# FPGA_0.net
KiCad netlist of a schematic drawn in Altium Designer
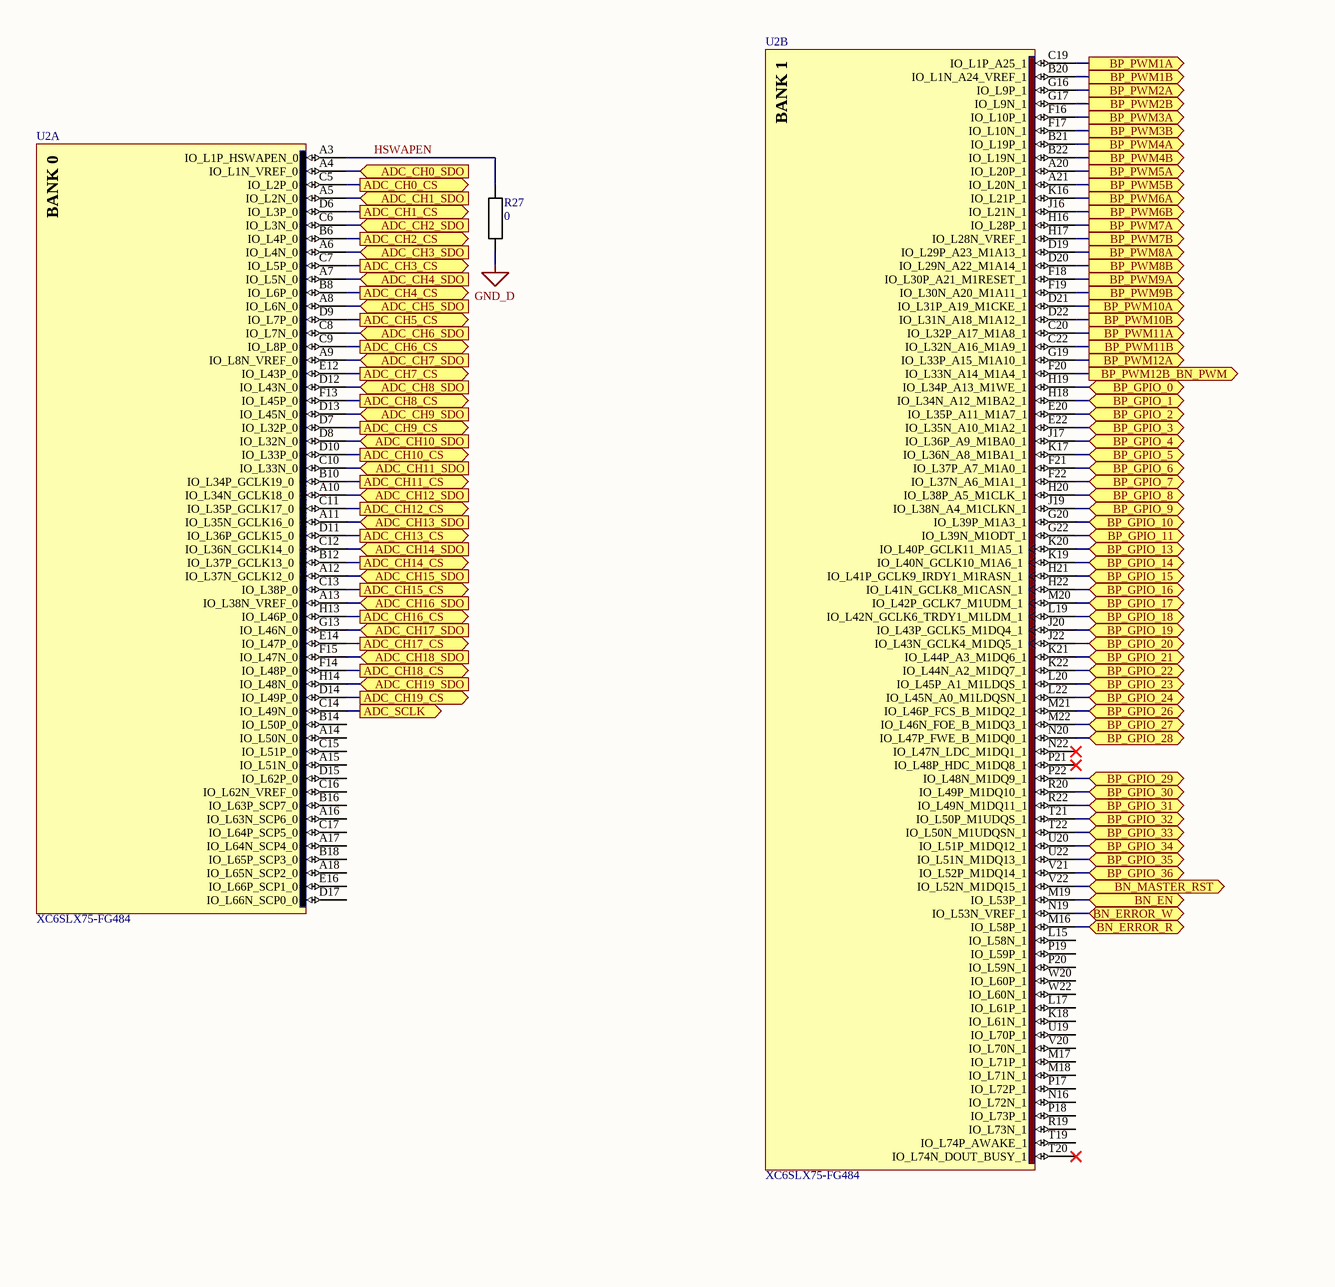
[diagram p0: FPGA_0.SchDoc, left]
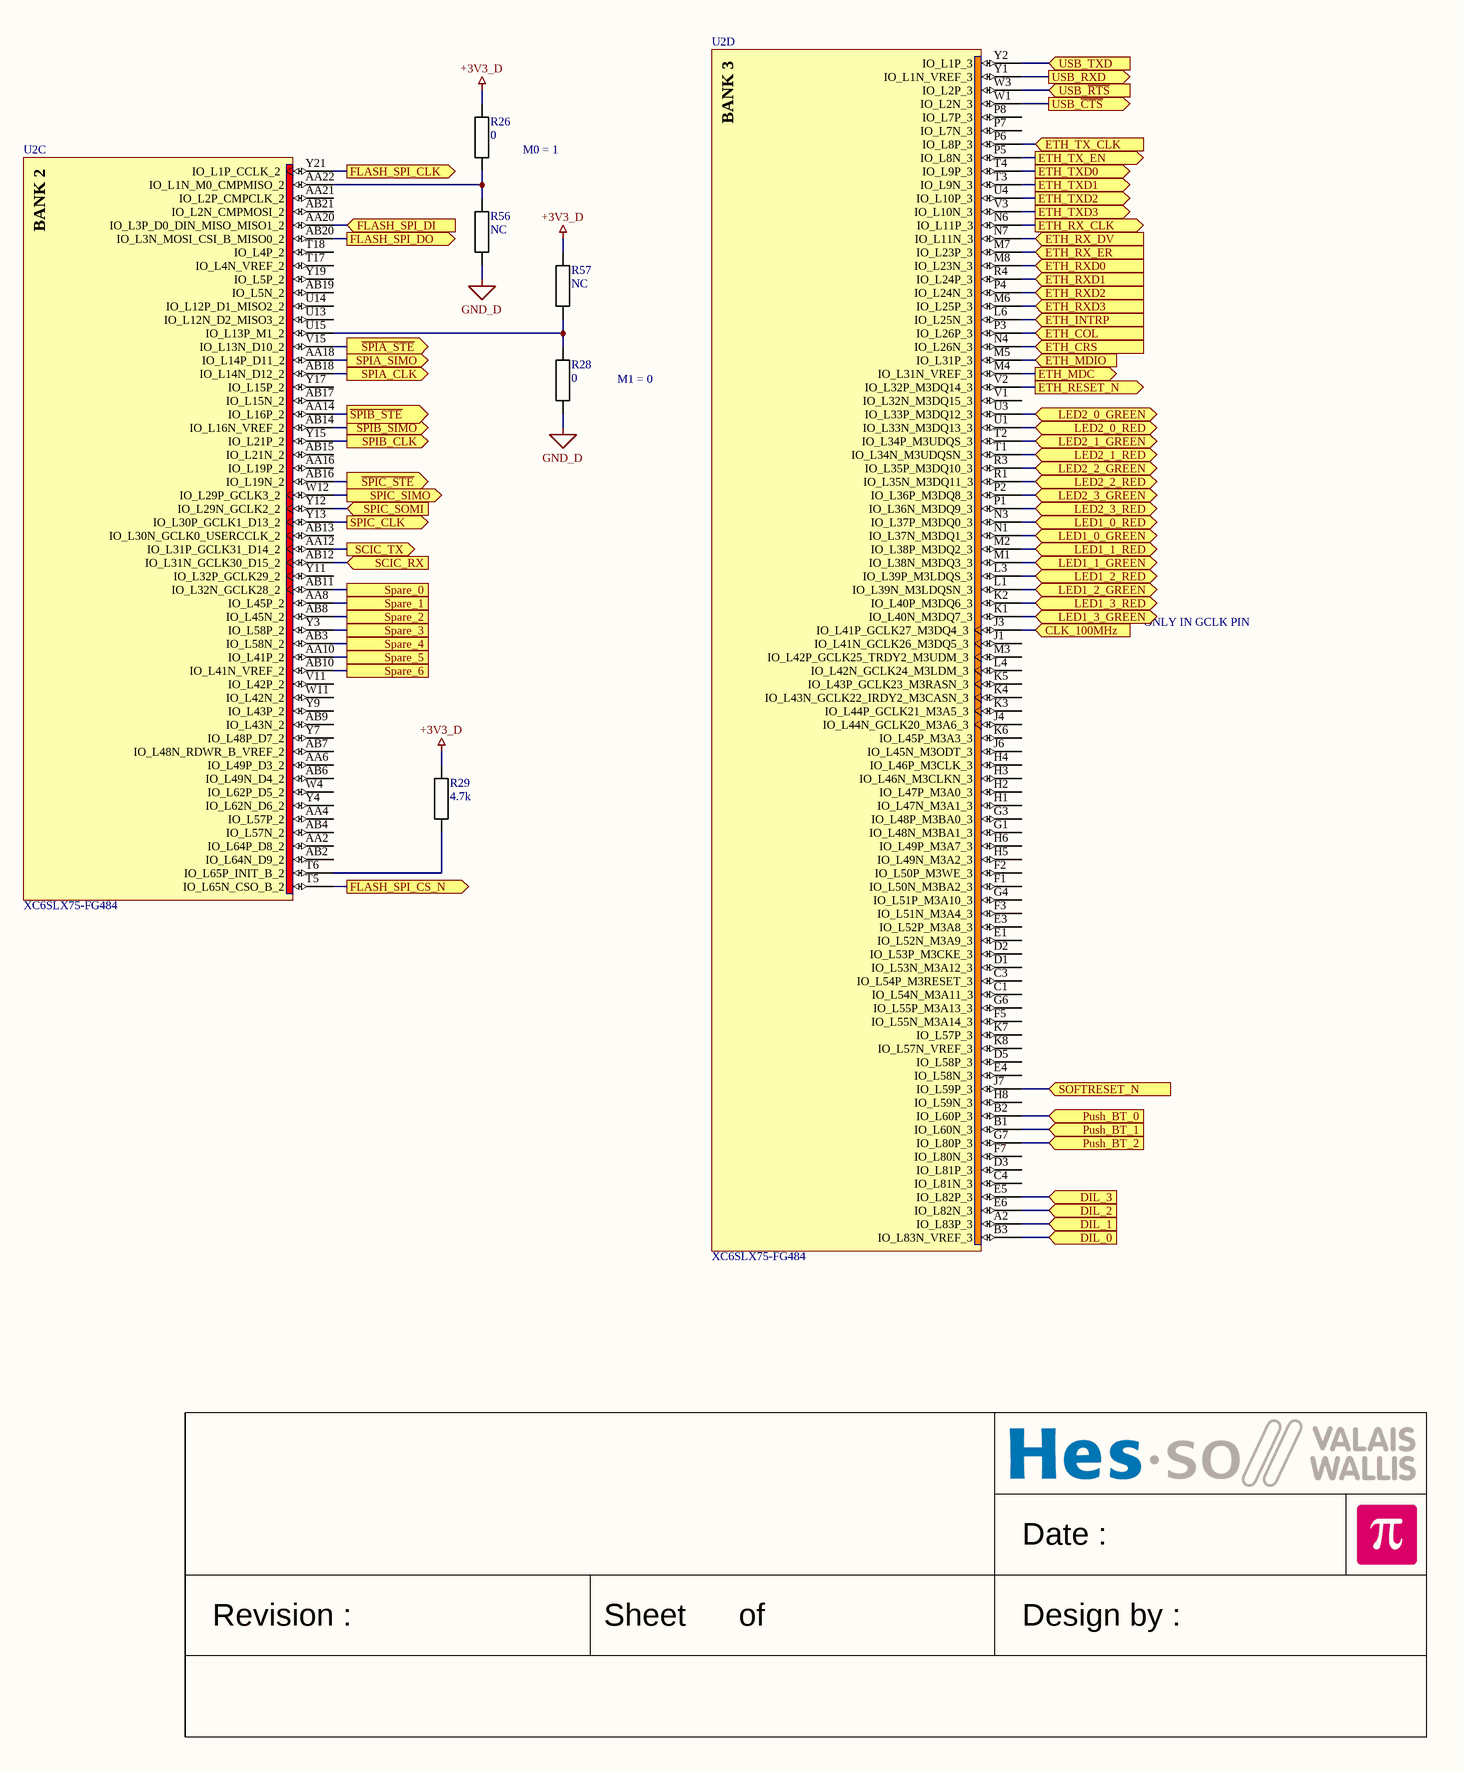
[diagram p1: FPGA_0.SchDoc, right]

(export (version "E")
  (design (tool "Eeschema 10.0.6"))
  (components
    (comp (ref "R26")
      (value "0")
      (footprint "RESISTOR 2012 REFLOW")
      (description "Resistor 1% 50V 125mW 2012(0805)")
      (libsource (lib "Resistor") (part "Resistor"))
    )
    (comp (ref "R27")
      (value "0")
      (footprint "RESISTOR 2012 REFLOW")
      (description "Resistor 1% 50V 125mW 2012(0805)")
      (libsource (lib "Resistor") (part "Resistor"))
    )
    (comp (ref "R28")
      (value "0")
      (footprint "RESISTOR 2012 REFLOW")
      (description "Resistor 1% 50V 125mW 2012(0805)")
      (libsource (lib "Resistor") (part "Resistor"))
    )
    (comp (ref "R29")
      (value "4.7k")
      (footprint "RESISTOR 2012 REFLOW")
      (description "Resistor 1% 50V 125mW 2012(0805)")
      (libsource (lib "Resistor") (part "Resistor"))
    )
    (comp (ref "R56")
      (value "NC")
      (footprint "RESISTOR 2012 REFLOW")
      (description "Resistor 1% 50V 125mW 2012(0805)")
      (libsource (lib "Resistor") (part "Resistor"))
    )
    (comp (ref "R57")
      (value "NC")
      (footprint "RESISTOR 2012 REFLOW")
      (description "Resistor 1% 50V 125mW 2012(0805)")
      (libsource (lib "Resistor") (part "Resistor"))
    )
    (comp (ref "U2")
      (value "XC6SLX75-FG484")
      (footprint "BGA484 P1.0 C23X23 H2.2")
      (description "Spartan-6 LXT 1.2V FPGA, 268 User I/Os, 484-Ball Fine-Pitch BGA (1.0mm Pitch)")
      (libsource (lib "Processor") (part "XC6SLX75-FG484"))
    )
  )
  (nets
    (net (code "1") (name "+3V3_D") (class "Default")
      (node (ref "R26") (pin "2") (pinfunction "2_2") (pintype "passive"))
      (node (ref "R29") (pin "2") (pinfunction "2_2") (pintype "passive"))
      (node (ref "R57") (pin "2") (pinfunction "2_2") (pintype "passive"))
    )
    (net (code "2") (name "/ADC_CH0_CS") (class "Default")
      (node (ref "U2") (pin "C5") (pinfunction "IO_L2P_0_C5") (pintype "bidirectional"))
    )
    (net (code "3") (name "/ADC_CH0_SDO") (class "Default")
      (node (ref "U2") (pin "A4") (pinfunction "IO_L1N_VREF_0_A4") (pintype "bidirectional"))
    )
    (net (code "4") (name "/ADC_CH1_CS") (class "Default")
      (node (ref "U2") (pin "D6") (pinfunction "IO_L3P_0_D6") (pintype "bidirectional"))
    )
    (net (code "5") (name "/ADC_CH1_SDO") (class "Default")
      (node (ref "U2") (pin "A5") (pinfunction "IO_L2N_0_A5") (pintype "bidirectional"))
    )
    (net (code "6") (name "/ADC_CH2_CS") (class "Default")
      (node (ref "U2") (pin "B6") (pinfunction "IO_L4P_0_B6") (pintype "bidirectional"))
    )
    (net (code "7") (name "/ADC_CH2_SDO") (class "Default")
      (node (ref "U2") (pin "C6") (pinfunction "IO_L3N_0_C6") (pintype "bidirectional"))
    )
    (net (code "8") (name "/ADC_CH3_CS") (class "Default")
      (node (ref "U2") (pin "C7") (pinfunction "IO_L5P_0_C7") (pintype "bidirectional"))
    )
    (net (code "9") (name "/ADC_CH3_SDO") (class "Default")
      (node (ref "U2") (pin "A6") (pinfunction "IO_L4N_0_A6") (pintype "bidirectional"))
    )
    (net (code "10") (name "/ADC_CH4_CS") (class "Default")
      (node (ref "U2") (pin "B8") (pinfunction "IO_L6P_0_B8") (pintype "bidirectional"))
    )
    (net (code "11") (name "/ADC_CH4_SDO") (class "Default")
      (node (ref "U2") (pin "A7") (pinfunction "IO_L5N_0_A7") (pintype "bidirectional"))
    )
    (net (code "12") (name "/ADC_CH5_CS") (class "Default")
      (node (ref "U2") (pin "D9") (pinfunction "IO_L7P_0_D9") (pintype "bidirectional"))
    )
    (net (code "13") (name "/ADC_CH5_SDO") (class "Default")
      (node (ref "U2") (pin "A8") (pinfunction "IO_L6N_0_A8") (pintype "bidirectional"))
    )
    (net (code "14") (name "/ADC_CH6_CS") (class "Default")
      (node (ref "U2") (pin "C9") (pinfunction "IO_L8P_0_C9") (pintype "bidirectional"))
    )
    (net (code "15") (name "/ADC_CH6_SDO") (class "Default")
      (node (ref "U2") (pin "C8") (pinfunction "IO_L7N_0_C8") (pintype "bidirectional"))
    )
    (net (code "16") (name "/ADC_CH7_CS") (class "Default")
      (node (ref "U2") (pin "E12") (pinfunction "IO_L43P_0_E12") (pintype "bidirectional"))
    )
    (net (code "17") (name "/ADC_CH7_SDO") (class "Default")
      (node (ref "U2") (pin "A9") (pinfunction "IO_L8N_VREF_0_A9") (pintype "bidirectional"))
    )
    (net (code "18") (name "/ADC_CH8_CS") (class "Default")
      (node (ref "U2") (pin "F13") (pinfunction "IO_L45P_0_F13") (pintype "bidirectional"))
    )
    (net (code "19") (name "/ADC_CH8_SDO") (class "Default")
      (node (ref "U2") (pin "D12") (pinfunction "IO_L43N_0_D12") (pintype "bidirectional"))
    )
    (net (code "20") (name "/ADC_CH9_CS") (class "Default")
      (node (ref "U2") (pin "D7") (pinfunction "IO_L32P_0_D7") (pintype "bidirectional"))
    )
    (net (code "21") (name "/ADC_CH9_SDO") (class "Default")
      (node (ref "U2") (pin "D13") (pinfunction "IO_L45N_0_D13") (pintype "bidirectional"))
    )
    (net (code "22") (name "/ADC_CH10_CS") (class "Default")
      (node (ref "U2") (pin "D10") (pinfunction "IO_L33P_0_D10") (pintype "bidirectional"))
    )
    (net (code "23") (name "/ADC_CH10_SDO") (class "Default")
      (node (ref "U2") (pin "D8") (pinfunction "IO_L32N_0_D8") (pintype "bidirectional"))
    )
    (net (code "24") (name "/ADC_CH11_CS") (class "Default")
      (node (ref "U2") (pin "B10") (pinfunction "IO_L34P_GCLK19_0_B10") (pintype "bidirectional"))
    )
    (net (code "25") (name "/ADC_CH11_SDO") (class "Default")
      (node (ref "U2") (pin "C10") (pinfunction "IO_L33N_0_C10") (pintype "bidirectional"))
    )
    (net (code "26") (name "/ADC_CH12_CS") (class "Default")
      (node (ref "U2") (pin "C11") (pinfunction "IO_L35P_GCLK17_0_C11") (pintype "bidirectional"))
    )
    (net (code "27") (name "/ADC_CH12_SDO") (class "Default")
      (node (ref "U2") (pin "A10") (pinfunction "IO_L34N_GCLK18_0_A10") (pintype "bidirectional"))
    )
    (net (code "28") (name "/ADC_CH13_CS") (class "Default")
      (node (ref "U2") (pin "D11") (pinfunction "IO_L36P_GCLK15_0_D11") (pintype "bidirectional"))
    )
    (net (code "29") (name "/ADC_CH13_SDO") (class "Default")
      (node (ref "U2") (pin "A11") (pinfunction "IO_L35N_GCLK16_0_A11") (pintype "bidirectional"))
    )
    (net (code "30") (name "/ADC_CH14_CS") (class "Default")
      (node (ref "U2") (pin "B12") (pinfunction "IO_L37P_GCLK13_0_B12") (pintype "bidirectional"))
    )
    (net (code "31") (name "/ADC_CH14_SDO") (class "Default")
      (node (ref "U2") (pin "C12") (pinfunction "IO_L36N_GCLK14_0_C12") (pintype "bidirectional"))
    )
    (net (code "32") (name "/ADC_CH15_CS") (class "Default")
      (node (ref "U2") (pin "C13") (pinfunction "IO_L38P_0_C13") (pintype "bidirectional"))
    )
    (net (code "33") (name "/ADC_CH15_SDO") (class "Default")
      (node (ref "U2") (pin "A12") (pinfunction "IO_L37N_GCLK12_0_A12") (pintype "bidirectional"))
    )
    (net (code "34") (name "/ADC_CH16_CS") (class "Default")
      (node (ref "U2") (pin "H13") (pinfunction "IO_L46P_0_H13") (pintype "bidirectional"))
    )
    (net (code "35") (name "/ADC_CH16_SDO") (class "Default")
      (node (ref "U2") (pin "A13") (pinfunction "IO_L38N_VREF_0_A13") (pintype "bidirectional"))
    )
    (net (code "36") (name "/ADC_CH17_CS") (class "Default")
      (node (ref "U2") (pin "E14") (pinfunction "IO_L47P_0_E14") (pintype "bidirectional"))
    )
    (net (code "37") (name "/ADC_CH17_SDO") (class "Default")
      (node (ref "U2") (pin "G13") (pinfunction "IO_L46N_0_G13") (pintype "bidirectional"))
    )
    (net (code "38") (name "/ADC_CH18_CS") (class "Default")
      (node (ref "U2") (pin "F14") (pinfunction "IO_L48P_0_F14") (pintype "bidirectional"))
    )
    (net (code "39") (name "/ADC_CH18_SDO") (class "Default")
      (node (ref "U2") (pin "F15") (pinfunction "IO_L47N_0_F15") (pintype "bidirectional"))
    )
    (net (code "40") (name "/ADC_CH19_CS") (class "Default")
      (node (ref "U2") (pin "D14") (pinfunction "IO_L49P_0_D14") (pintype "bidirectional"))
    )
    (net (code "41") (name "/ADC_CH19_SDO") (class "Default")
      (node (ref "U2") (pin "H14") (pinfunction "IO_L48N_0_H14") (pintype "bidirectional"))
    )
    (net (code "42") (name "/ADC_SCLK") (class "Default")
      (node (ref "U2") (pin "C14") (pinfunction "IO_L49N_0_C14") (pintype "bidirectional"))
    )
    (net (code "43") (name "/BN_EN") (class "Default")
      (node (ref "U2") (pin "M19") (pinfunction "IO_L53P_1_M19") (pintype "bidirectional"))
    )
    (net (code "44") (name "/BN_ERROR_R") (class "Default")
      (node (ref "U2") (pin "M16") (pinfunction "IO_L58P_1_M16") (pintype "bidirectional"))
    )
    (net (code "45") (name "/BN_ERROR_W") (class "Default")
      (node (ref "U2") (pin "N19") (pinfunction "IO_L53N_VREF_1_N19") (pintype "bidirectional"))
    )
    (net (code "46") (name "/BN_MASTER_RST") (class "Default")
      (node (ref "U2") (pin "V22") (pinfunction "IO_L52N_M1DQ15_1_V22") (pintype "bidirectional"))
    )
    (net (code "47") (name "/BP_GPIO_0") (class "Default")
      (node (ref "U2") (pin "H19") (pinfunction "IO_L34P_A13_M1WE_1_H19") (pintype "bidirectional"))
    )
    (net (code "48") (name "/BP_GPIO_1") (class "Default")
      (node (ref "U2") (pin "H18") (pinfunction "IO_L34N_A12_M1BA2_1_H18") (pintype "bidirectional"))
    )
    (net (code "49") (name "/BP_GPIO_2") (class "Default")
      (node (ref "U2") (pin "E20") (pinfunction "IO_L35P_A11_M1A7_1_E20") (pintype "bidirectional"))
    )
    (net (code "50") (name "/BP_GPIO_3") (class "Default")
      (node (ref "U2") (pin "E22") (pinfunction "IO_L35N_A10_M1A2_1_E22") (pintype "bidirectional"))
    )
    (net (code "51") (name "/BP_GPIO_4") (class "Default")
      (node (ref "U2") (pin "J17") (pinfunction "IO_L36P_A9_M1BA0_1_J17") (pintype "bidirectional"))
    )
    (net (code "52") (name "/BP_GPIO_5") (class "Default")
      (node (ref "U2") (pin "K17") (pinfunction "IO_L36N_A8_M1BA1_1_K17") (pintype "bidirectional"))
    )
    (net (code "53") (name "/BP_GPIO_6") (class "Default")
      (node (ref "U2") (pin "F21") (pinfunction "IO_L37P_A7_M1A0_1_F21") (pintype "bidirectional"))
    )
    (net (code "54") (name "/BP_GPIO_7") (class "Default")
      (node (ref "U2") (pin "F22") (pinfunction "IO_L37N_A6_M1A1_1_F22") (pintype "bidirectional"))
    )
    (net (code "55") (name "/BP_GPIO_8") (class "Default")
      (node (ref "U2") (pin "H20") (pinfunction "IO_L38P_A5_M1CLK_1_H20") (pintype "bidirectional"))
    )
    (net (code "56") (name "/BP_GPIO_9") (class "Default")
      (node (ref "U2") (pin "J19") (pinfunction "IO_L38N_A4_M1CLKN_1_J19") (pintype "bidirectional"))
    )
    (net (code "57") (name "/BP_GPIO_10") (class "Default")
      (node (ref "U2") (pin "G20") (pinfunction "IO_L39P_M1A3_1_G20") (pintype "bidirectional"))
    )
    (net (code "58") (name "/BP_GPIO_11") (class "Default")
      (node (ref "U2") (pin "G22") (pinfunction "IO_L39N_M1ODT_1_G22") (pintype "bidirectional"))
    )
    (net (code "59") (name "/BP_GPIO_13") (class "Default")
      (node (ref "U2") (pin "K20") (pinfunction "IO_L40P_GCLK11_M1A5_1_K20") (pintype "bidirectional"))
    )
    (net (code "60") (name "/BP_GPIO_14") (class "Default")
      (node (ref "U2") (pin "K19") (pinfunction "IO_L40N_GCLK10_M1A6_1_K19") (pintype "bidirectional"))
    )
    (net (code "61") (name "/BP_GPIO_15") (class "Default")
      (node (ref "U2") (pin "H21") (pinfunction "IO_L41P_GCLK9_IRDY1_M1RASN_1_H21") (pintype "bidirectional"))
    )
    (net (code "62") (name "/BP_GPIO_16") (class "Default")
      (node (ref "U2") (pin "H22") (pinfunction "IO_L41N_GCLK8_M1CASN_1_H22") (pintype "bidirectional"))
    )
    (net (code "63") (name "/BP_GPIO_17") (class "Default")
      (node (ref "U2") (pin "M20") (pinfunction "IO_L42P_GCLK7_M1UDM_1_M20") (pintype "bidirectional"))
    )
    (net (code "64") (name "/BP_GPIO_18") (class "Default")
      (node (ref "U2") (pin "L19") (pinfunction "IO_L42N_GCLK6_TRDY1_M1LDM_1_L19") (pintype "bidirectional"))
    )
    (net (code "65") (name "/BP_GPIO_19") (class "Default")
      (node (ref "U2") (pin "J20") (pinfunction "IO_L43P_GCLK5_M1DQ4_1_J20") (pintype "bidirectional"))
    )
    (net (code "66") (name "/BP_GPIO_20") (class "Default")
      (node (ref "U2") (pin "J22") (pinfunction "IO_L43N_GCLK4_M1DQ5_1_J22") (pintype "bidirectional"))
    )
    (net (code "67") (name "/BP_GPIO_21") (class "Default")
      (node (ref "U2") (pin "K21") (pinfunction "IO_L44P_A3_M1DQ6_1_K21") (pintype "bidirectional"))
    )
    (net (code "68") (name "/BP_GPIO_22") (class "Default")
      (node (ref "U2") (pin "K22") (pinfunction "IO_L44N_A2_M1DQ7_1_K22") (pintype "bidirectional"))
    )
    (net (code "69") (name "/BP_GPIO_23") (class "Default")
      (node (ref "U2") (pin "L20") (pinfunction "IO_L45P_A1_M1LDQS_1_L20") (pintype "bidirectional"))
    )
    (net (code "70") (name "/BP_GPIO_24") (class "Default")
      (node (ref "U2") (pin "L22") (pinfunction "IO_L45N_A0_M1LDQSN_1_L22") (pintype "bidirectional"))
    )
    (net (code "71") (name "/BP_GPIO_26") (class "Default")
      (node (ref "U2") (pin "M21") (pinfunction "IO_L46P_FCS_B_M1DQ2_1_M21") (pintype "bidirectional"))
    )
    (net (code "72") (name "/BP_GPIO_27") (class "Default")
      (node (ref "U2") (pin "M22") (pinfunction "IO_L46N_FOE_B_M1DQ3_1_M22") (pintype "bidirectional"))
    )
    (net (code "73") (name "/BP_GPIO_28") (class "Default")
      (node (ref "U2") (pin "N20") (pinfunction "IO_L47P_FWE_B_M1DQ0_1_N20") (pintype "bidirectional"))
    )
    (net (code "74") (name "/BP_GPIO_29") (class "Default")
      (node (ref "U2") (pin "P22") (pinfunction "IO_L48N_M1DQ9_1_P22") (pintype "bidirectional"))
    )
    (net (code "75") (name "/BP_GPIO_30") (class "Default")
      (node (ref "U2") (pin "R20") (pinfunction "IO_L49P_M1DQ10_1_R20") (pintype "bidirectional"))
    )
    (net (code "76") (name "/BP_GPIO_31") (class "Default")
      (node (ref "U2") (pin "R22") (pinfunction "IO_L49N_M1DQ11_1_R22") (pintype "bidirectional"))
    )
    (net (code "77") (name "/BP_GPIO_32") (class "Default")
      (node (ref "U2") (pin "T21") (pinfunction "IO_L50P_M1UDQS_1_T21") (pintype "bidirectional"))
    )
    (net (code "78") (name "/BP_GPIO_33") (class "Default")
      (node (ref "U2") (pin "T22") (pinfunction "IO_L50N_M1UDQSN_1_T22") (pintype "bidirectional"))
    )
    (net (code "79") (name "/BP_GPIO_34") (class "Default")
      (node (ref "U2") (pin "U20") (pinfunction "IO_L51P_M1DQ12_1_U20") (pintype "bidirectional"))
    )
    (net (code "80") (name "/BP_GPIO_35") (class "Default")
      (node (ref "U2") (pin "U22") (pinfunction "IO_L51N_M1DQ13_1_U22") (pintype "bidirectional"))
    )
    (net (code "81") (name "/BP_GPIO_36") (class "Default")
      (node (ref "U2") (pin "V21") (pinfunction "IO_L52P_M1DQ14_1_V21") (pintype "bidirectional"))
    )
    (net (code "82") (name "/BP_PWM1A") (class "Default")
      (node (ref "U2") (pin "C19") (pinfunction "IO_L1P_A25_1_C19") (pintype "bidirectional"))
    )
    (net (code "83") (name "/BP_PWM1B") (class "Default")
      (node (ref "U2") (pin "B20") (pinfunction "IO_L1N_A24_VREF_1_B20") (pintype "bidirectional"))
    )
    (net (code "84") (name "/BP_PWM2A") (class "Default")
      (node (ref "U2") (pin "G16") (pinfunction "IO_L9P_1_G16") (pintype "bidirectional"))
    )
    (net (code "85") (name "/BP_PWM2B") (class "Default")
      (node (ref "U2") (pin "G17") (pinfunction "IO_L9N_1_G17") (pintype "bidirectional"))
    )
    (net (code "86") (name "/BP_PWM3A") (class "Default")
      (node (ref "U2") (pin "F16") (pinfunction "IO_L10P_1_F16") (pintype "bidirectional"))
    )
    (net (code "87") (name "/BP_PWM3B") (class "Default")
      (node (ref "U2") (pin "F17") (pinfunction "IO_L10N_1_F17") (pintype "bidirectional"))
    )
    (net (code "88") (name "/BP_PWM4A") (class "Default")
      (node (ref "U2") (pin "B21") (pinfunction "IO_L19P_1_B21") (pintype "bidirectional"))
    )
    (net (code "89") (name "/BP_PWM4B") (class "Default")
      (node (ref "U2") (pin "B22") (pinfunction "IO_L19N_1_B22") (pintype "bidirectional"))
    )
    (net (code "90") (name "/BP_PWM5A") (class "Default")
      (node (ref "U2") (pin "A20") (pinfunction "IO_L20P_1_A20") (pintype "bidirectional"))
    )
    (net (code "91") (name "/BP_PWM5B") (class "Default")
      (node (ref "U2") (pin "A21") (pinfunction "IO_L20N_1_A21") (pintype "bidirectional"))
    )
    (net (code "92") (name "/BP_PWM6A") (class "Default")
      (node (ref "U2") (pin "K16") (pinfunction "IO_L21P_1_K16") (pintype "bidirectional"))
    )
    (net (code "93") (name "/BP_PWM6B") (class "Default")
      (node (ref "U2") (pin "J16") (pinfunction "IO_L21N_1_J16") (pintype "bidirectional"))
    )
    (net (code "94") (name "/BP_PWM7A") (class "Default")
      (node (ref "U2") (pin "H16") (pinfunction "IO_L28P_1_H16") (pintype "bidirectional"))
    )
    (net (code "95") (name "/BP_PWM7B") (class "Default")
      (node (ref "U2") (pin "H17") (pinfunction "IO_L28N_VREF_1_H17") (pintype "bidirectional"))
    )
    (net (code "96") (name "/BP_PWM8A") (class "Default")
      (node (ref "U2") (pin "D19") (pinfunction "IO_L29P_A23_M1A13_1_D19") (pintype "bidirectional"))
    )
    (net (code "97") (name "/BP_PWM8B") (class "Default")
      (node (ref "U2") (pin "D20") (pinfunction "IO_L29N_A22_M1A14_1_D20") (pintype "bidirectional"))
    )
    (net (code "98") (name "/BP_PWM9A") (class "Default")
      (node (ref "U2") (pin "F18") (pinfunction "IO_L30P_A21_M1RESET_1_F18") (pintype "bidirectional"))
    )
    (net (code "99") (name "/BP_PWM9B") (class "Default")
      (node (ref "U2") (pin "F19") (pinfunction "IO_L30N_A20_M1A11_1_F19") (pintype "bidirectional"))
    )
    (net (code "100") (name "/BP_PWM10A") (class "Default")
      (node (ref "U2") (pin "D21") (pinfunction "IO_L31P_A19_M1CKE_1_D21") (pintype "bidirectional"))
    )
    (net (code "101") (name "/BP_PWM10B") (class "Default")
      (node (ref "U2") (pin "D22") (pinfunction "IO_L31N_A18_M1A12_1_D22") (pintype "bidirectional"))
    )
    (net (code "102") (name "/BP_PWM11A") (class "Default")
      (node (ref "U2") (pin "C20") (pinfunction "IO_L32P_A17_M1A8_1_C20") (pintype "bidirectional"))
    )
    (net (code "103") (name "/BP_PWM11B") (class "Default")
      (node (ref "U2") (pin "C22") (pinfunction "IO_L32N_A16_M1A9_1_C22") (pintype "bidirectional"))
    )
    (net (code "104") (name "/BP_PWM12A") (class "Default")
      (node (ref "U2") (pin "G19") (pinfunction "IO_L33P_A15_M1A10_1_G19") (pintype "bidirectional"))
    )
    (net (code "105") (name "/BP_PWM12B_BN_PWM") (class "Default")
      (node (ref "U2") (pin "F20") (pinfunction "IO_L33N_A14_M1A4_1_F20") (pintype "bidirectional"))
    )
    (net (code "106") (name "/CLK_100MHz") (class "Default")
      (node (ref "U2") (pin "J3") (pinfunction "IO_L41P_GCLK27_M3DQ4_3_J3") (pintype "bidirectional"))
    )
    (net (code "107") (name "/DIL_0") (class "Default")
      (node (ref "U2") (pin "B3") (pinfunction "IO_L83N_VREF_3_B3") (pintype "bidirectional"))
    )
    (net (code "108") (name "/DIL_1") (class "Default")
      (node (ref "U2") (pin "A2") (pinfunction "IO_L83P_3_A2") (pintype "bidirectional"))
    )
    (net (code "109") (name "/DIL_2") (class "Default")
      (node (ref "U2") (pin "E6") (pinfunction "IO_L82N_3_E6") (pintype "bidirectional"))
    )
    (net (code "110") (name "/DIL_3") (class "Default")
      (node (ref "U2") (pin "E5") (pinfunction "IO_L82P_3_E5") (pintype "bidirectional"))
    )
    (net (code "111") (name "/ETH_COL") (class "Default")
      (node (ref "U2") (pin "P3") (pinfunction "IO_L26P_3_P3") (pintype "bidirectional"))
    )
    (net (code "112") (name "/ETH_CRS") (class "Default")
      (node (ref "U2") (pin "N4") (pinfunction "IO_L26N_3_N4") (pintype "bidirectional"))
    )
    (net (code "113") (name "/ETH_INTRP") (class "Default")
      (node (ref "U2") (pin "L6") (pinfunction "IO_L25N_3_L6") (pintype "bidirectional"))
    )
    (net (code "114") (name "/ETH_MDC") (class "Default")
      (node (ref "U2") (pin "M4") (pinfunction "IO_L31N_VREF_3_M4") (pintype "bidirectional"))
    )
    (net (code "115") (name "/ETH_MDIO") (class "Default")
      (node (ref "U2") (pin "M5") (pinfunction "IO_L31P_3_M5") (pintype "bidirectional"))
    )
    (net (code "116") (name "/ETH_RESET_N") (class "Default")
      (node (ref "U2") (pin "V2") (pinfunction "IO_L32P_M3DQ14_3_V2") (pintype "bidirectional"))
    )
    (net (code "117") (name "/ETH_RXD0") (class "Default")
      (node (ref "U2") (pin "M8") (pinfunction "IO_L23N_3_M8") (pintype "bidirectional"))
    )
    (net (code "118") (name "/ETH_RXD1") (class "Default")
      (node (ref "U2") (pin "R4") (pinfunction "IO_L24P_3_R4") (pintype "bidirectional"))
    )
    (net (code "119") (name "/ETH_RXD2") (class "Default")
      (node (ref "U2") (pin "P4") (pinfunction "IO_L24N_3_P4") (pintype "bidirectional"))
    )
    (net (code "120") (name "/ETH_RXD3") (class "Default")
      (node (ref "U2") (pin "M6") (pinfunction "IO_L25P_3_M6") (pintype "bidirectional"))
    )
    (net (code "121") (name "/ETH_RX_CLK") (class "Default")
      (node (ref "U2") (pin "N6") (pinfunction "IO_L11P_3_N6") (pintype "bidirectional"))
    )
    (net (code "122") (name "/ETH_RX_DV") (class "Default")
      (node (ref "U2") (pin "N7") (pinfunction "IO_L11N_3_N7") (pintype "bidirectional"))
    )
    (net (code "123") (name "/ETH_RX_ER") (class "Default")
      (node (ref "U2") (pin "M7") (pinfunction "IO_L23P_3_M7") (pintype "bidirectional"))
    )
    (net (code "124") (name "/ETH_TXD0") (class "Default")
      (node (ref "U2") (pin "T4") (pinfunction "IO_L9P_3_T4") (pintype "bidirectional"))
    )
    (net (code "125") (name "/ETH_TXD1") (class "Default")
      (node (ref "U2") (pin "T3") (pinfunction "IO_L9N_3_T3") (pintype "bidirectional"))
    )
    (net (code "126") (name "/ETH_TXD2") (class "Default")
      (node (ref "U2") (pin "U4") (pinfunction "IO_L10P_3_U4") (pintype "bidirectional"))
    )
    (net (code "127") (name "/ETH_TXD3") (class "Default")
      (node (ref "U2") (pin "V3") (pinfunction "IO_L10N_3_V3") (pintype "bidirectional"))
    )
    (net (code "128") (name "/ETH_TX_CLK") (class "Default")
      (node (ref "U2") (pin "P6") (pinfunction "IO_L8P_3_P6") (pintype "bidirectional"))
    )
    (net (code "129") (name "/ETH_TX_EN") (class "Default")
      (node (ref "U2") (pin "P5") (pinfunction "IO_L8N_3_P5") (pintype "bidirectional"))
    )
    (net (code "130") (name "/FLASH_SPI_CLK") (class "Default")
      (node (ref "U2") (pin "Y21") (pinfunction "IO_L1P_CCLK_2_Y21") (pintype "bidirectional"))
    )
    (net (code "131") (name "/FLASH_SPI_CS_N") (class "Default")
      (node (ref "U2") (pin "T5") (pinfunction "IO_L65N_CSO_B_2_T5") (pintype "bidirectional"))
    )
    (net (code "132") (name "/FLASH_SPI_DI") (class "Default")
      (node (ref "U2") (pin "AA20") (pinfunction "IO_L3P_D0_DIN_MISO_MISO1_2_AA20") (pintype "bidirectional"))
    )
    (net (code "133") (name "/FLASH_SPI_DO") (class "Default")
      (node (ref "U2") (pin "AB20") (pinfunction "IO_L3N_MOSI_CSI_B_MISO0_2_AB20") (pintype "bidirectional"))
    )
    (net (code "134") (name "/HSWAPEN") (class "Default")
      (node (ref "R27") (pin "2") (pinfunction "2_2") (pintype "passive"))
      (node (ref "U2") (pin "A3") (pinfunction "IO_L1P_HSWAPEN_0_A3") (pintype "bidirectional"))
    )
    (net (code "135") (name "/LED1_0_GREEN") (class "Default")
      (node (ref "U2") (pin "N1") (pinfunction "IO_L37N_M3DQ1_3_N1") (pintype "bidirectional"))
    )
    (net (code "136") (name "/LED1_0_RED") (class "Default")
      (node (ref "U2") (pin "N3") (pinfunction "IO_L37P_M3DQ0_3_N3") (pintype "bidirectional"))
    )
    (net (code "137") (name "/LED1_1_GREEN") (class "Default")
      (node (ref "U2") (pin "M1") (pinfunction "IO_L38N_M3DQ3_3_M1") (pintype "bidirectional"))
    )
    (net (code "138") (name "/LED1_1_RED") (class "Default")
      (node (ref "U2") (pin "M2") (pinfunction "IO_L38P_M3DQ2_3_M2") (pintype "bidirectional"))
    )
    (net (code "139") (name "/LED1_2_GREEN") (class "Default")
      (node (ref "U2") (pin "L1") (pinfunction "IO_L39N_M3LDQSN_3_L1") (pintype "bidirectional"))
    )
    (net (code "140") (name "/LED1_2_RED") (class "Default")
      (node (ref "U2") (pin "L3") (pinfunction "IO_L39P_M3LDQS_3_L3") (pintype "bidirectional"))
    )
    (net (code "141") (name "/LED1_3_GREEN") (class "Default")
      (node (ref "U2") (pin "K1") (pinfunction "IO_L40N_M3DQ7_3_K1") (pintype "bidirectional"))
    )
    (net (code "142") (name "/LED1_3_RED") (class "Default")
      (node (ref "U2") (pin "K2") (pinfunction "IO_L40P_M3DQ6_3_K2") (pintype "bidirectional"))
    )
    (net (code "143") (name "/LED2_0_GREEN") (class "Default")
      (node (ref "U2") (pin "U3") (pinfunction "IO_L33P_M3DQ12_3_U3") (pintype "bidirectional"))
    )
    (net (code "144") (name "/LED2_0_RED") (class "Default")
      (node (ref "U2") (pin "U1") (pinfunction "IO_L33N_M3DQ13_3_U1") (pintype "bidirectional"))
    )
    (net (code "145") (name "/LED2_1_GREEN") (class "Default")
      (node (ref "U2") (pin "T2") (pinfunction "IO_L34P_M3UDQS_3_T2") (pintype "bidirectional"))
    )
    (net (code "146") (name "/LED2_1_RED") (class "Default")
      (node (ref "U2") (pin "T1") (pinfunction "IO_L34N_M3UDQSN_3_T1") (pintype "bidirectional"))
    )
    (net (code "147") (name "/LED2_2_GREEN") (class "Default")
      (node (ref "U2") (pin "R3") (pinfunction "IO_L35P_M3DQ10_3_R3") (pintype "bidirectional"))
    )
    (net (code "148") (name "/LED2_2_RED") (class "Default")
      (node (ref "U2") (pin "R1") (pinfunction "IO_L35N_M3DQ11_3_R1") (pintype "bidirectional"))
    )
    (net (code "149") (name "/LED2_3_GREEN") (class "Default")
      (node (ref "U2") (pin "P2") (pinfunction "IO_L36P_M3DQ8_3_P2") (pintype "bidirectional"))
    )
    (net (code "150") (name "/LED2_3_RED") (class "Default")
      (node (ref "U2") (pin "P1") (pinfunction "IO_L36N_M3DQ9_3_P1") (pintype "bidirectional"))
    )
    (net (code "151") (name "/Push_BT_0") (class "Default")
      (node (ref "U2") (pin "B2") (pinfunction "IO_L60P_3_B2") (pintype "bidirectional"))
    )
    (net (code "152") (name "/Push_BT_1") (class "Default")
      (node (ref "U2") (pin "B1") (pinfunction "IO_L60N_3_B1") (pintype "bidirectional"))
    )
    (net (code "153") (name "/Push_BT_2") (class "Default")
      (node (ref "U2") (pin "G7") (pinfunction "IO_L80P_3_G7") (pintype "bidirectional"))
    )
    (net (code "154") (name "/SCIC_RX") (class "Default")
      (node (ref "U2") (pin "AB12") (pinfunction "IO_L31N_GCLK30_D15_2_AB12") (pintype "bidirectional"))
    )
    (net (code "155") (name "/SCIC_TX") (class "Default")
      (node (ref "U2") (pin "AA12") (pinfunction "IO_L31P_GCLK31_D14_2_AA12") (pintype "bidirectional"))
    )
    (net (code "156") (name "/SOFTRESET_N") (class "Default")
      (node (ref "U2") (pin "J7") (pinfunction "IO_L59P_3_J7") (pintype "bidirectional"))
    )
    (net (code "157") (name "/SPIA_CLK") (class "Default")
      (node (ref "U2") (pin "AB18") (pinfunction "IO_L14N_D12_2_AB18") (pintype "bidirectional"))
    )
    (net (code "158") (name "/SPIA_SIMO") (class "Default")
      (node (ref "U2") (pin "AA18") (pinfunction "IO_L14P_D11_2_AA18") (pintype "bidirectional"))
    )
    (net (code "159") (name "/SPIB_CLK") (class "Default")
      (node (ref "U2") (pin "Y15") (pinfunction "IO_L21P_2_Y15") (pintype "bidirectional"))
    )
    (net (code "160") (name "/SPIB_SIMO") (class "Default")
      (node (ref "U2") (pin "AB14") (pinfunction "IO_L16N_VREF_2_AB14") (pintype "bidirectional"))
    )
    (net (code "161") (name "/SPIC_CLK") (class "Default")
      (node (ref "U2") (pin "Y13") (pinfunction "IO_L30P_GCLK1_D13_2_Y13") (pintype "bidirectional"))
    )
    (net (code "162") (name "/SPIC_SIMO") (class "Default")
      (node (ref "U2") (pin "W12") (pinfunction "IO_L29P_GCLK3_2_W12") (pintype "bidirectional"))
    )
    (net (code "163") (name "/SPIC_SOMI") (class "Default")
      (node (ref "U2") (pin "Y12") (pinfunction "IO_L29N_GCLK2_2_Y12") (pintype "bidirectional"))
    )
    (net (code "164") (name "/Spare_0") (class "Default")
      (node (ref "U2") (pin "AB11") (pinfunction "IO_L32N_GCLK28_2_AB11") (pintype "bidirectional"))
    )
    (net (code "165") (name "/Spare_1") (class "Default")
      (node (ref "U2") (pin "AA8") (pinfunction "IO_L45P_2_AA8") (pintype "bidirectional"))
    )
    (net (code "166") (name "/Spare_2") (class "Default")
      (node (ref "U2") (pin "AB8") (pinfunction "IO_L45N_2_AB8") (pintype "bidirectional"))
    )
    (net (code "167") (name "/Spare_3") (class "Default")
      (node (ref "U2") (pin "Y3") (pinfunction "IO_L58P_2_Y3") (pintype "bidirectional"))
    )
    (net (code "168") (name "/Spare_4") (class "Default")
      (node (ref "U2") (pin "AB3") (pinfunction "IO_L58N_2_AB3") (pintype "bidirectional"))
    )
    (net (code "169") (name "/Spare_5") (class "Default")
      (node (ref "U2") (pin "AA10") (pinfunction "IO_L41P_2_AA10") (pintype "bidirectional"))
    )
    (net (code "170") (name "/Spare_6") (class "Default")
      (node (ref "U2") (pin "AB10") (pinfunction "IO_L41N_VREF_2_AB10") (pintype "bidirectional"))
    )
    (net (code "171") (name "/USB_RXD") (class "Default")
      (node (ref "U2") (pin "Y1") (pinfunction "IO_L1N_VREF_3_Y1") (pintype "bidirectional"))
    )
    (net (code "172") (name "/USB_TXD") (class "Default")
      (node (ref "U2") (pin "Y2") (pinfunction "IO_L1P_3_Y2") (pintype "bidirectional"))
    )
    (net (code "173") (name "/USB_~{CTS}") (class "Default")
      (node (ref "U2") (pin "W1") (pinfunction "IO_L2N_3_W1") (pintype "bidirectional"))
    )
    (net (code "174") (name "/USB_~{RTS}") (class "Default")
      (node (ref "U2") (pin "W3") (pinfunction "IO_L2P_3_W3") (pintype "bidirectional"))
    )
    (net (code "175") (name "/~{SPIA_STE}") (class "Default")
      (node (ref "U2") (pin "V15") (pinfunction "IO_L13N_D10_2_V15") (pintype "bidirectional"))
    )
    (net (code "176") (name "/~{SPIB_STE}") (class "Default")
      (node (ref "U2") (pin "AA14") (pinfunction "IO_L16P_2_AA14") (pintype "bidirectional"))
    )
    (net (code "177") (name "/~{SPIC_STE}") (class "Default")
      (node (ref "U2") (pin "AB16") (pinfunction "IO_L19N_2_AB16") (pintype "bidirectional"))
    )
    (net (code "178") (name "GND_D") (class "Default")
      (node (ref "R27") (pin "1") (pinfunction "1_1") (pintype "passive"))
      (node (ref "R28") (pin "1") (pinfunction "1_1") (pintype "passive"))
      (node (ref "R56") (pin "1") (pinfunction "1_1") (pintype "passive"))
    )
    (net (code "179") (name "Net-(U2C-IO_L1N_M0_CMPMISO_2)") (class "Default")
      (node (ref "R26") (pin "1") (pinfunction "1_1") (pintype "passive"))
      (node (ref "R56") (pin "2") (pinfunction "2_2") (pintype "passive"))
      (node (ref "U2") (pin "AA22") (pinfunction "IO_L1N_M0_CMPMISO_2_AA22") (pintype "bidirectional"))
    )
    (net (code "180") (name "Net-(U2C-IO_L13P_M1_2)") (class "Default")
      (node (ref "R28") (pin "2") (pinfunction "2_2") (pintype "passive"))
      (node (ref "R57") (pin "1") (pinfunction "1_1") (pintype "passive"))
      (node (ref "U2") (pin "U15") (pinfunction "IO_L13P_M1_2_U15") (pintype "bidirectional"))
    )
    (net (code "181") (name "Net-(U2C-IO_L65P_INIT_B_2)") (class "Default")
      (node (ref "R29") (pin "1") (pinfunction "1_1") (pintype "passive"))
      (node (ref "U2") (pin "T6") (pinfunction "IO_L65P_INIT_B_2_T6") (pintype "bidirectional"))
    )
    (net (code "182") (name "unconnected-(U2A-IO_L50N_0-PadA14)") (class "Default")
      (node (ref "U2") (pin "A14") (pinfunction "IO_L50N_0_A14") (pintype "bidirectional"))
    )
    (net (code "183") (name "unconnected-(U2A-IO_L50P_0-PadB14)") (class "Default")
      (node (ref "U2") (pin "B14") (pinfunction "IO_L50P_0_B14") (pintype "bidirectional"))
    )
    (net (code "184") (name "unconnected-(U2A-IO_L51N_0-PadA15)") (class "Default")
      (node (ref "U2") (pin "A15") (pinfunction "IO_L51N_0_A15") (pintype "bidirectional"))
    )
    (net (code "185") (name "unconnected-(U2A-IO_L51P_0-PadC15)") (class "Default")
      (node (ref "U2") (pin "C15") (pinfunction "IO_L51P_0_C15") (pintype "bidirectional"))
    )
    (net (code "186") (name "unconnected-(U2A-IO_L62N_VREF_0-PadC16)") (class "Default")
      (node (ref "U2") (pin "C16") (pinfunction "IO_L62N_VREF_0_C16") (pintype "bidirectional"))
    )
    (net (code "187") (name "unconnected-(U2A-IO_L62P_0-PadD15)") (class "Default")
      (node (ref "U2") (pin "D15") (pinfunction "IO_L62P_0_D15") (pintype "bidirectional"))
    )
    (net (code "188") (name "unconnected-(U2A-IO_L63N_SCP6_0-PadA16)") (class "Default")
      (node (ref "U2") (pin "A16") (pinfunction "IO_L63N_SCP6_0_A16") (pintype "bidirectional"))
    )
    (net (code "189") (name "unconnected-(U2A-IO_L63P_SCP7_0-PadB16)") (class "Default")
      (node (ref "U2") (pin "B16") (pinfunction "IO_L63P_SCP7_0_B16") (pintype "bidirectional"))
    )
    (net (code "190") (name "unconnected-(U2A-IO_L64N_SCP4_0-PadA17)") (class "Default")
      (node (ref "U2") (pin "A17") (pinfunction "IO_L64N_SCP4_0_A17") (pintype "bidirectional"))
    )
    (net (code "191") (name "unconnected-(U2A-IO_L64P_SCP5_0-PadC17)") (class "Default")
      (node (ref "U2") (pin "C17") (pinfunction "IO_L64P_SCP5_0_C17") (pintype "bidirectional"))
    )
    (net (code "192") (name "unconnected-(U2A-IO_L65N_SCP2_0-PadA18)") (class "Default")
      (node (ref "U2") (pin "A18") (pinfunction "IO_L65N_SCP2_0_A18") (pintype "bidirectional"))
    )
    (net (code "193") (name "unconnected-(U2A-IO_L65P_SCP3_0-PadB18)") (class "Default")
      (node (ref "U2") (pin "B18") (pinfunction "IO_L65P_SCP3_0_B18") (pintype "bidirectional"))
    )
    (net (code "194") (name "unconnected-(U2A-IO_L66N_SCP0_0-PadD17)") (class "Default")
      (node (ref "U2") (pin "D17") (pinfunction "IO_L66N_SCP0_0_D17") (pintype "bidirectional"))
    )
    (net (code "195") (name "unconnected-(U2A-IO_L66P_SCP1_0-PadE16)") (class "Default")
      (node (ref "U2") (pin "E16") (pinfunction "IO_L66P_SCP1_0_E16") (pintype "bidirectional"))
    )
    (net (code "196") (name "unconnected-(U2B-IO_L47N_LDC_M1DQ1_1-PadN22)") (class "Default")
      (node (ref "U2") (pin "N22") (pinfunction "IO_L47N_LDC_M1DQ1_1_N22") (pintype "bidirectional+no_connect"))
    )
    (net (code "197") (name "unconnected-(U2B-IO_L48P_HDC_M1DQ8_1-PadP21)") (class "Default")
      (node (ref "U2") (pin "P21") (pinfunction "IO_L48P_HDC_M1DQ8_1_P21") (pintype "bidirectional+no_connect"))
    )
    (net (code "198") (name "unconnected-(U2B-IO_L58N_1-PadL15)") (class "Default")
      (node (ref "U2") (pin "L15") (pinfunction "IO_L58N_1_L15") (pintype "bidirectional"))
    )
    (net (code "199") (name "unconnected-(U2B-IO_L59N_1-PadP20)") (class "Default")
      (node (ref "U2") (pin "P20") (pinfunction "IO_L59N_1_P20") (pintype "bidirectional"))
    )
    (net (code "200") (name "unconnected-(U2B-IO_L59P_1-PadP19)") (class "Default")
      (node (ref "U2") (pin "P19") (pinfunction "IO_L59P_1_P19") (pintype "bidirectional"))
    )
    (net (code "201") (name "unconnected-(U2B-IO_L60N_1-PadW22)") (class "Default")
      (node (ref "U2") (pin "W22") (pinfunction "IO_L60N_1_W22") (pintype "bidirectional"))
    )
    (net (code "202") (name "unconnected-(U2B-IO_L60P_1-PadW20)") (class "Default")
      (node (ref "U2") (pin "W20") (pinfunction "IO_L60P_1_W20") (pintype "bidirectional"))
    )
    (net (code "203") (name "unconnected-(U2B-IO_L61N_1-PadK18)") (class "Default")
      (node (ref "U2") (pin "K18") (pinfunction "IO_L61N_1_K18") (pintype "bidirectional"))
    )
    (net (code "204") (name "unconnected-(U2B-IO_L61P_1-PadL17)") (class "Default")
      (node (ref "U2") (pin "L17") (pinfunction "IO_L61P_1_L17") (pintype "bidirectional"))
    )
    (net (code "205") (name "unconnected-(U2B-IO_L70N_1-PadV20)") (class "Default")
      (node (ref "U2") (pin "V20") (pinfunction "IO_L70N_1_V20") (pintype "bidirectional"))
    )
    (net (code "206") (name "unconnected-(U2B-IO_L70P_1-PadU19)") (class "Default")
      (node (ref "U2") (pin "U19") (pinfunction "IO_L70P_1_U19") (pintype "bidirectional"))
    )
    (net (code "207") (name "unconnected-(U2B-IO_L71N_1-PadM18)") (class "Default")
      (node (ref "U2") (pin "M18") (pinfunction "IO_L71N_1_M18") (pintype "bidirectional"))
    )
    (net (code "208") (name "unconnected-(U2B-IO_L71P_1-PadM17)") (class "Default")
      (node (ref "U2") (pin "M17") (pinfunction "IO_L71P_1_M17") (pintype "bidirectional"))
    )
    (net (code "209") (name "unconnected-(U2B-IO_L72N_1-PadN16)") (class "Default")
      (node (ref "U2") (pin "N16") (pinfunction "IO_L72N_1_N16") (pintype "bidirectional"))
    )
    (net (code "210") (name "unconnected-(U2B-IO_L72P_1-PadP17)") (class "Default")
      (node (ref "U2") (pin "P17") (pinfunction "IO_L72P_1_P17") (pintype "bidirectional"))
    )
    (net (code "211") (name "unconnected-(U2B-IO_L73N_1-PadR19)") (class "Default")
      (node (ref "U2") (pin "R19") (pinfunction "IO_L73N_1_R19") (pintype "bidirectional"))
    )
    (net (code "212") (name "unconnected-(U2B-IO_L73P_1-PadP18)") (class "Default")
      (node (ref "U2") (pin "P18") (pinfunction "IO_L73P_1_P18") (pintype "bidirectional"))
    )
    (net (code "213") (name "unconnected-(U2B-IO_L74N_DOUT_BUSY_1-PadT20)") (class "Default")
      (node (ref "U2") (pin "T20") (pinfunction "IO_L74N_DOUT_BUSY_1_T20") (pintype "bidirectional+no_connect"))
    )
    (net (code "214") (name "unconnected-(U2B-IO_L74P_AWAKE_1-PadT19)") (class "Default")
      (node (ref "U2") (pin "T19") (pinfunction "IO_L74P_AWAKE_1_T19") (pintype "bidirectional"))
    )
    (net (code "215") (name "unconnected-(U2C-IO_L2N_CMPMOSI_2-PadAB21)") (class "Default")
      (node (ref "U2") (pin "AB21") (pinfunction "IO_L2N_CMPMOSI_2_AB21") (pintype "bidirectional"))
    )
    (net (code "216") (name "unconnected-(U2C-IO_L2P_CMPCLK_2-PadAA21)") (class "Default")
      (node (ref "U2") (pin "AA21") (pinfunction "IO_L2P_CMPCLK_2_AA21") (pintype "bidirectional"))
    )
    (net (code "217") (name "unconnected-(U2C-IO_L4N_VREF_2-PadT17)") (class "Default")
      (node (ref "U2") (pin "T17") (pinfunction "IO_L4N_VREF_2_T17") (pintype "bidirectional"))
    )
    (net (code "218") (name "unconnected-(U2C-IO_L4P_2-PadT18)") (class "Default")
      (node (ref "U2") (pin "T18") (pinfunction "IO_L4P_2_T18") (pintype "bidirectional"))
    )
    (net (code "219") (name "unconnected-(U2C-IO_L5N_2-PadAB19)") (class "Default")
      (node (ref "U2") (pin "AB19") (pinfunction "IO_L5N_2_AB19") (pintype "bidirectional"))
    )
    (net (code "220") (name "unconnected-(U2C-IO_L5P_2-PadY19)") (class "Default")
      (node (ref "U2") (pin "Y19") (pinfunction "IO_L5P_2_Y19") (pintype "bidirectional"))
    )
    (net (code "221") (name "unconnected-(U2C-IO_L12N_D2_MISO3_2-PadU13)") (class "Default")
      (node (ref "U2") (pin "U13") (pinfunction "IO_L12N_D2_MISO3_2_U13") (pintype "bidirectional"))
    )
    (net (code "222") (name "unconnected-(U2C-IO_L12P_D1_MISO2_2-PadU14)") (class "Default")
      (node (ref "U2") (pin "U14") (pinfunction "IO_L12P_D1_MISO2_2_U14") (pintype "bidirectional"))
    )
    (net (code "223") (name "unconnected-(U2C-IO_L15N_2-PadAB17)") (class "Default")
      (node (ref "U2") (pin "AB17") (pinfunction "IO_L15N_2_AB17") (pintype "bidirectional"))
    )
    (net (code "224") (name "unconnected-(U2C-IO_L15P_2-PadY17)") (class "Default")
      (node (ref "U2") (pin "Y17") (pinfunction "IO_L15P_2_Y17") (pintype "bidirectional"))
    )
    (net (code "225") (name "unconnected-(U2C-IO_L19P_2-PadAA16)") (class "Default")
      (node (ref "U2") (pin "AA16") (pinfunction "IO_L19P_2_AA16") (pintype "bidirectional"))
    )
    (net (code "226") (name "unconnected-(U2C-IO_L21N_2-PadAB15)") (class "Default")
      (node (ref "U2") (pin "AB15") (pinfunction "IO_L21N_2_AB15") (pintype "bidirectional"))
    )
    (net (code "227") (name "unconnected-(U2C-IO_L30N_GCLK0_USERCCLK_2-PadAB13)") (class "Default")
      (node (ref "U2") (pin "AB13") (pinfunction "IO_L30N_GCLK0_USERCCLK_2_AB13") (pintype "bidirectional"))
    )
    (net (code "228") (name "unconnected-(U2C-IO_L32P_GCLK29_2-PadY11)") (class "Default")
      (node (ref "U2") (pin "Y11") (pinfunction "IO_L32P_GCLK29_2_Y11") (pintype "bidirectional"))
    )
    (net (code "229") (name "unconnected-(U2C-IO_L42N_2-PadW11)") (class "Default")
      (node (ref "U2") (pin "W11") (pinfunction "IO_L42N_2_W11") (pintype "bidirectional"))
    )
    (net (code "230") (name "unconnected-(U2C-IO_L42P_2-PadV11)") (class "Default")
      (node (ref "U2") (pin "V11") (pinfunction "IO_L42P_2_V11") (pintype "bidirectional"))
    )
    (net (code "231") (name "unconnected-(U2C-IO_L43N_2-PadAB9)") (class "Default")
      (node (ref "U2") (pin "AB9") (pinfunction "IO_L43N_2_AB9") (pintype "bidirectional"))
    )
    (net (code "232") (name "unconnected-(U2C-IO_L43P_2-PadY9)") (class "Default")
      (node (ref "U2") (pin "Y9") (pinfunction "IO_L43P_2_Y9") (pintype "bidirectional"))
    )
    (net (code "233") (name "unconnected-(U2C-IO_L48N_RDWR_B_VREF_2-PadAB7)") (class "Default")
      (node (ref "U2") (pin "AB7") (pinfunction "IO_L48N_RDWR_B_VREF_2_AB7") (pintype "bidirectional"))
    )
    (net (code "234") (name "unconnected-(U2C-IO_L48P_D7_2-PadY7)") (class "Default")
      (node (ref "U2") (pin "Y7") (pinfunction "IO_L48P_D7_2_Y7") (pintype "bidirectional"))
    )
    (net (code "235") (name "unconnected-(U2C-IO_L49N_D4_2-PadAB6)") (class "Default")
      (node (ref "U2") (pin "AB6") (pinfunction "IO_L49N_D4_2_AB6") (pintype "bidirectional"))
    )
    (net (code "236") (name "unconnected-(U2C-IO_L49P_D3_2-PadAA6)") (class "Default")
      (node (ref "U2") (pin "AA6") (pinfunction "IO_L49P_D3_2_AA6") (pintype "bidirectional"))
    )
    (net (code "237") (name "unconnected-(U2C-IO_L57N_2-PadAB4)") (class "Default")
      (node (ref "U2") (pin "AB4") (pinfunction "IO_L57N_2_AB4") (pintype "bidirectional"))
    )
    (net (code "238") (name "unconnected-(U2C-IO_L57P_2-PadAA4)") (class "Default")
      (node (ref "U2") (pin "AA4") (pinfunction "IO_L57P_2_AA4") (pintype "bidirectional"))
    )
    (net (code "239") (name "unconnected-(U2C-IO_L62N_D6_2-PadY4)") (class "Default")
      (node (ref "U2") (pin "Y4") (pinfunction "IO_L62N_D6_2_Y4") (pintype "bidirectional"))
    )
    (net (code "240") (name "unconnected-(U2C-IO_L62P_D5_2-PadW4)") (class "Default")
      (node (ref "U2") (pin "W4") (pinfunction "IO_L62P_D5_2_W4") (pintype "bidirectional"))
    )
    (net (code "241") (name "unconnected-(U2C-IO_L64N_D9_2-PadAB2)") (class "Default")
      (node (ref "U2") (pin "AB2") (pinfunction "IO_L64N_D9_2_AB2") (pintype "bidirectional"))
    )
    (net (code "242") (name "unconnected-(U2C-IO_L64P_D8_2-PadAA2)") (class "Default")
      (node (ref "U2") (pin "AA2") (pinfunction "IO_L64P_D8_2_AA2") (pintype "bidirectional"))
    )
    (net (code "243") (name "unconnected-(U2D-IO_L7N_3-PadP7)") (class "Default")
      (node (ref "U2") (pin "P7") (pinfunction "IO_L7N_3_P7") (pintype "bidirectional"))
    )
    (net (code "244") (name "unconnected-(U2D-IO_L7P_3-PadP8)") (class "Default")
      (node (ref "U2") (pin "P8") (pinfunction "IO_L7P_3_P8") (pintype "bidirectional"))
    )
    (net (code "245") (name "unconnected-(U2D-IO_L32N_M3DQ15_3-PadV1)") (class "Default")
      (node (ref "U2") (pin "V1") (pinfunction "IO_L32N_M3DQ15_3_V1") (pintype "bidirectional"))
    )
    (net (code "246") (name "unconnected-(U2D-IO_L41N_GCLK26_M3DQ5_3-PadJ1)") (class "Default")
      (node (ref "U2") (pin "J1") (pinfunction "IO_L41N_GCLK26_M3DQ5_3_J1") (pintype "bidirectional"))
    )
    (net (code "247") (name "unconnected-(U2D-IO_L42N_GCLK24_M3LDM_3-PadL4)") (class "Default")
      (node (ref "U2") (pin "L4") (pinfunction "IO_L42N_GCLK24_M3LDM_3_L4") (pintype "bidirectional"))
    )
    (net (code "248") (name "unconnected-(U2D-IO_L42P_GCLK25_TRDY2_M3UDM_3-PadM3)") (class "Default")
      (node (ref "U2") (pin "M3") (pinfunction "IO_L42P_GCLK25_TRDY2_M3UDM_3_M3") (pintype "bidirectional"))
    )
    (net (code "249") (name "unconnected-(U2D-IO_L43N_GCLK22_IRDY2_M3CASN_3-PadK4)") (class "Default")
      (node (ref "U2") (pin "K4") (pinfunction "IO_L43N_GCLK22_IRDY2_M3CASN_3_K4") (pintype "bidirectional"))
    )
    (net (code "250") (name "unconnected-(U2D-IO_L43P_GCLK23_M3RASN_3-PadK5)") (class "Default")
      (node (ref "U2") (pin "K5") (pinfunction "IO_L43P_GCLK23_M3RASN_3_K5") (pintype "bidirectional"))
    )
    (net (code "251") (name "unconnected-(U2D-IO_L44N_GCLK20_M3A6_3-PadJ4)") (class "Default")
      (node (ref "U2") (pin "J4") (pinfunction "IO_L44N_GCLK20_M3A6_3_J4") (pintype "bidirectional"))
    )
    (net (code "252") (name "unconnected-(U2D-IO_L44P_GCLK21_M3A5_3-PadK3)") (class "Default")
      (node (ref "U2") (pin "K3") (pinfunction "IO_L44P_GCLK21_M3A5_3_K3") (pintype "bidirectional"))
    )
    (net (code "253") (name "unconnected-(U2D-IO_L45N_M3ODT_3-PadJ6)") (class "Default")
      (node (ref "U2") (pin "J6") (pinfunction "IO_L45N_M3ODT_3_J6") (pintype "bidirectional"))
    )
    (net (code "254") (name "unconnected-(U2D-IO_L45P_M3A3_3-PadK6)") (class "Default")
      (node (ref "U2") (pin "K6") (pinfunction "IO_L45P_M3A3_3_K6") (pintype "bidirectional"))
    )
    (net (code "255") (name "unconnected-(U2D-IO_L46N_M3CLKN_3-PadH3)") (class "Default")
      (node (ref "U2") (pin "H3") (pinfunction "IO_L46N_M3CLKN_3_H3") (pintype "bidirectional"))
    )
    (net (code "256") (name "unconnected-(U2D-IO_L46P_M3CLK_3-PadH4)") (class "Default")
      (node (ref "U2") (pin "H4") (pinfunction "IO_L46P_M3CLK_3_H4") (pintype "bidirectional"))
    )
    (net (code "257") (name "unconnected-(U2D-IO_L47N_M3A1_3-PadH1)") (class "Default")
      (node (ref "U2") (pin "H1") (pinfunction "IO_L47N_M3A1_3_H1") (pintype "bidirectional"))
    )
    (net (code "258") (name "unconnected-(U2D-IO_L47P_M3A0_3-PadH2)") (class "Default")
      (node (ref "U2") (pin "H2") (pinfunction "IO_L47P_M3A0_3_H2") (pintype "bidirectional"))
    )
    (net (code "259") (name "unconnected-(U2D-IO_L48N_M3BA1_3-PadG1)") (class "Default")
      (node (ref "U2") (pin "G1") (pinfunction "IO_L48N_M3BA1_3_G1") (pintype "bidirectional"))
    )
    (net (code "260") (name "unconnected-(U2D-IO_L48P_M3BA0_3-PadG3)") (class "Default")
      (node (ref "U2") (pin "G3") (pinfunction "IO_L48P_M3BA0_3_G3") (pintype "bidirectional"))
    )
    (net (code "261") (name "unconnected-(U2D-IO_L49N_M3A2_3-PadH5)") (class "Default")
      (node (ref "U2") (pin "H5") (pinfunction "IO_L49N_M3A2_3_H5") (pintype "bidirectional"))
    )
    (net (code "262") (name "unconnected-(U2D-IO_L49P_M3A7_3-PadH6)") (class "Default")
      (node (ref "U2") (pin "H6") (pinfunction "IO_L49P_M3A7_3_H6") (pintype "bidirectional"))
    )
    (net (code "263") (name "unconnected-(U2D-IO_L50N_M3BA2_3-PadF1)") (class "Default")
      (node (ref "U2") (pin "F1") (pinfunction "IO_L50N_M3BA2_3_F1") (pintype "bidirectional"))
    )
    (net (code "264") (name "unconnected-(U2D-IO_L50P_M3WE_3-PadF2)") (class "Default")
      (node (ref "U2") (pin "F2") (pinfunction "IO_L50P_M3WE_3_F2") (pintype "bidirectional"))
    )
    (net (code "265") (name "unconnected-(U2D-IO_L51N_M3A4_3-PadF3)") (class "Default")
      (node (ref "U2") (pin "F3") (pinfunction "IO_L51N_M3A4_3_F3") (pintype "bidirectional"))
    )
    (net (code "266") (name "unconnected-(U2D-IO_L51P_M3A10_3-PadG4)") (class "Default")
      (node (ref "U2") (pin "G4") (pinfunction "IO_L51P_M3A10_3_G4") (pintype "bidirectional"))
    )
    (net (code "267") (name "unconnected-(U2D-IO_L52N_M3A9_3-PadE1)") (class "Default")
      (node (ref "U2") (pin "E1") (pinfunction "IO_L52N_M3A9_3_E1") (pintype "bidirectional"))
    )
    (net (code "268") (name "unconnected-(U2D-IO_L52P_M3A8_3-PadE3)") (class "Default")
      (node (ref "U2") (pin "E3") (pinfunction "IO_L52P_M3A8_3_E3") (pintype "bidirectional"))
    )
    (net (code "269") (name "unconnected-(U2D-IO_L53N_M3A12_3-PadD1)") (class "Default")
      (node (ref "U2") (pin "D1") (pinfunction "IO_L53N_M3A12_3_D1") (pintype "bidirectional"))
    )
    (net (code "270") (name "unconnected-(U2D-IO_L53P_M3CKE_3-PadD2)") (class "Default")
      (node (ref "U2") (pin "D2") (pinfunction "IO_L53P_M3CKE_3_D2") (pintype "bidirectional"))
    )
    (net (code "271") (name "unconnected-(U2D-IO_L54N_M3A11_3-PadC1)") (class "Default")
      (node (ref "U2") (pin "C1") (pinfunction "IO_L54N_M3A11_3_C1") (pintype "bidirectional"))
    )
    (net (code "272") (name "unconnected-(U2D-IO_L54P_M3RESET_3-PadC3)") (class "Default")
      (node (ref "U2") (pin "C3") (pinfunction "IO_L54P_M3RESET_3_C3") (pintype "bidirectional"))
    )
    (net (code "273") (name "unconnected-(U2D-IO_L55N_M3A14_3-PadF5)") (class "Default")
      (node (ref "U2") (pin "F5") (pinfunction "IO_L55N_M3A14_3_F5") (pintype "bidirectional"))
    )
    (net (code "274") (name "unconnected-(U2D-IO_L55P_M3A13_3-PadG6)") (class "Default")
      (node (ref "U2") (pin "G6") (pinfunction "IO_L55P_M3A13_3_G6") (pintype "bidirectional"))
    )
    (net (code "275") (name "unconnected-(U2D-IO_L57N_VREF_3-PadK8)") (class "Default")
      (node (ref "U2") (pin "K8") (pinfunction "IO_L57N_VREF_3_K8") (pintype "bidirectional"))
    )
    (net (code "276") (name "unconnected-(U2D-IO_L57P_3-PadK7)") (class "Default")
      (node (ref "U2") (pin "K7") (pinfunction "IO_L57P_3_K7") (pintype "bidirectional"))
    )
    (net (code "277") (name "unconnected-(U2D-IO_L58N_3-PadE4)") (class "Default")
      (node (ref "U2") (pin "E4") (pinfunction "IO_L58N_3_E4") (pintype "bidirectional"))
    )
    (net (code "278") (name "unconnected-(U2D-IO_L58P_3-PadD5)") (class "Default")
      (node (ref "U2") (pin "D5") (pinfunction "IO_L58P_3_D5") (pintype "bidirectional"))
    )
    (net (code "279") (name "unconnected-(U2D-IO_L59N_3-PadH8)") (class "Default")
      (node (ref "U2") (pin "H8") (pinfunction "IO_L59N_3_H8") (pintype "bidirectional"))
    )
    (net (code "280") (name "unconnected-(U2D-IO_L80N_3-PadF7)") (class "Default")
      (node (ref "U2") (pin "F7") (pinfunction "IO_L80N_3_F7") (pintype "bidirectional"))
    )
    (net (code "281") (name "unconnected-(U2D-IO_L81N_3-PadC4)") (class "Default")
      (node (ref "U2") (pin "C4") (pinfunction "IO_L81N_3_C4") (pintype "bidirectional"))
    )
    (net (code "282") (name "unconnected-(U2D-IO_L81P_3-PadD3)") (class "Default")
      (node (ref "U2") (pin "D3") (pinfunction "IO_L81P_3_D3") (pintype "bidirectional"))
    )
  )
)
